# USBi.net
KiCad netlist of a schematic drawn in Altium Designer
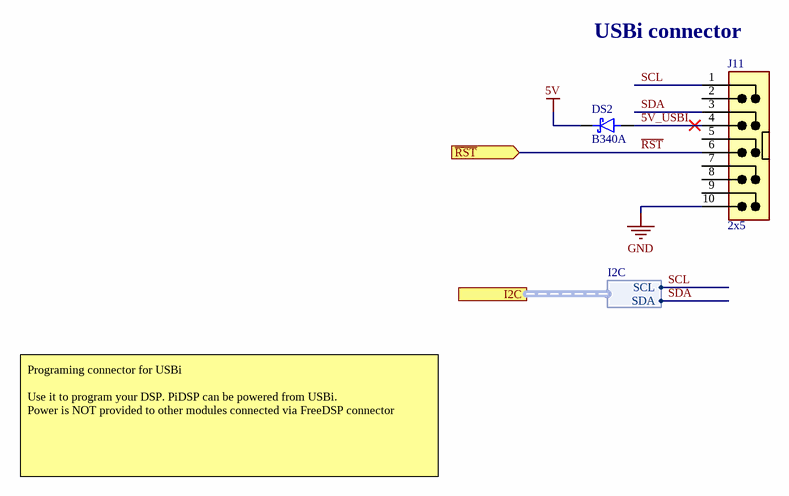
[diagram p0: USBi.SchDoc]

(export (version "E")
  (design (tool "Eeschema 10.0.6"))
  (components
    (comp (ref "DS2")
      (value "B340A")
      (footprint "DIOM5127X23N(SMA)")
      (description "High Current Density SMT Schottky Rectifier, 3A/40V, SMA")
      (libsource (lib "JP_IC") (part "B340A"))
    )
    (comp (ref "J11")
      (value "2x5")
      (footprint "MLW10G_BK")
      (description "IDC Male Header for PCB 2x5 Pin, Straight")
      (fields (field (name "AUTHOR") "JM 25.9.2014"))
      (libsource (lib "JP_CONN") (part "MLW 2x5"))
    )
  )
  (nets
    (net (code "2") (name "/5V_USBI") (class "Default")
      (node (ref "DS2") (pin "2") (pinfunction "A_2") (pintype "passive"))
      (node (ref "J11") (pin "4") (pinfunction "4_4") (pintype "passive"))
    )
    (net (code "3") (name "/SCL") (class "Default")
      (node (ref "J11") (pin "1") (pinfunction "1_1") (pintype "passive"))
    )
    (net (code "4") (name "/SDA") (class "Default")
      (node (ref "J11") (pin "3") (pinfunction "3_3") (pintype "passive"))
    )
    (net (code "6") (name "/~{RST}") (class "Default")
      (node (ref "J11") (pin "6") (pinfunction "6_6") (pintype "passive"))
    )
    (net (code "7") (name "5V") (class "Default")
      (node (ref "DS2") (pin "1") (pinfunction "C_1") (pintype "passive"))
    )
    (net (code "8") (name "GND") (class "Default")
      (node (ref "J11") (pin "10") (pinfunction "10_10") (pintype "passive"))
    )
    (net (code "9") (name "unconnected-(J11-Pad2)") (class "Default")
      (node (ref "J11") (pin "2") (pinfunction "2_2") (pintype "passive"))
    )
    (net (code "10") (name "unconnected-(J11-Pad5)") (class "Default")
      (node (ref "J11") (pin "5") (pinfunction "5_5") (pintype "passive"))
    )
    (net (code "11") (name "unconnected-(J11-Pad7)") (class "Default")
      (node (ref "J11") (pin "7") (pinfunction "7_7") (pintype "passive"))
    )
    (net (code "12") (name "unconnected-(J11-Pad8)") (class "Default")
      (node (ref "J11") (pin "8") (pinfunction "8_8") (pintype "passive"))
    )
    (net (code "13") (name "unconnected-(J11-Pad9)") (class "Default")
      (node (ref "J11") (pin "9") (pinfunction "9_9") (pintype "passive"))
    )
  )
)
